# opamp.net
KiCad netlist of a schematic drawn in EAGLE
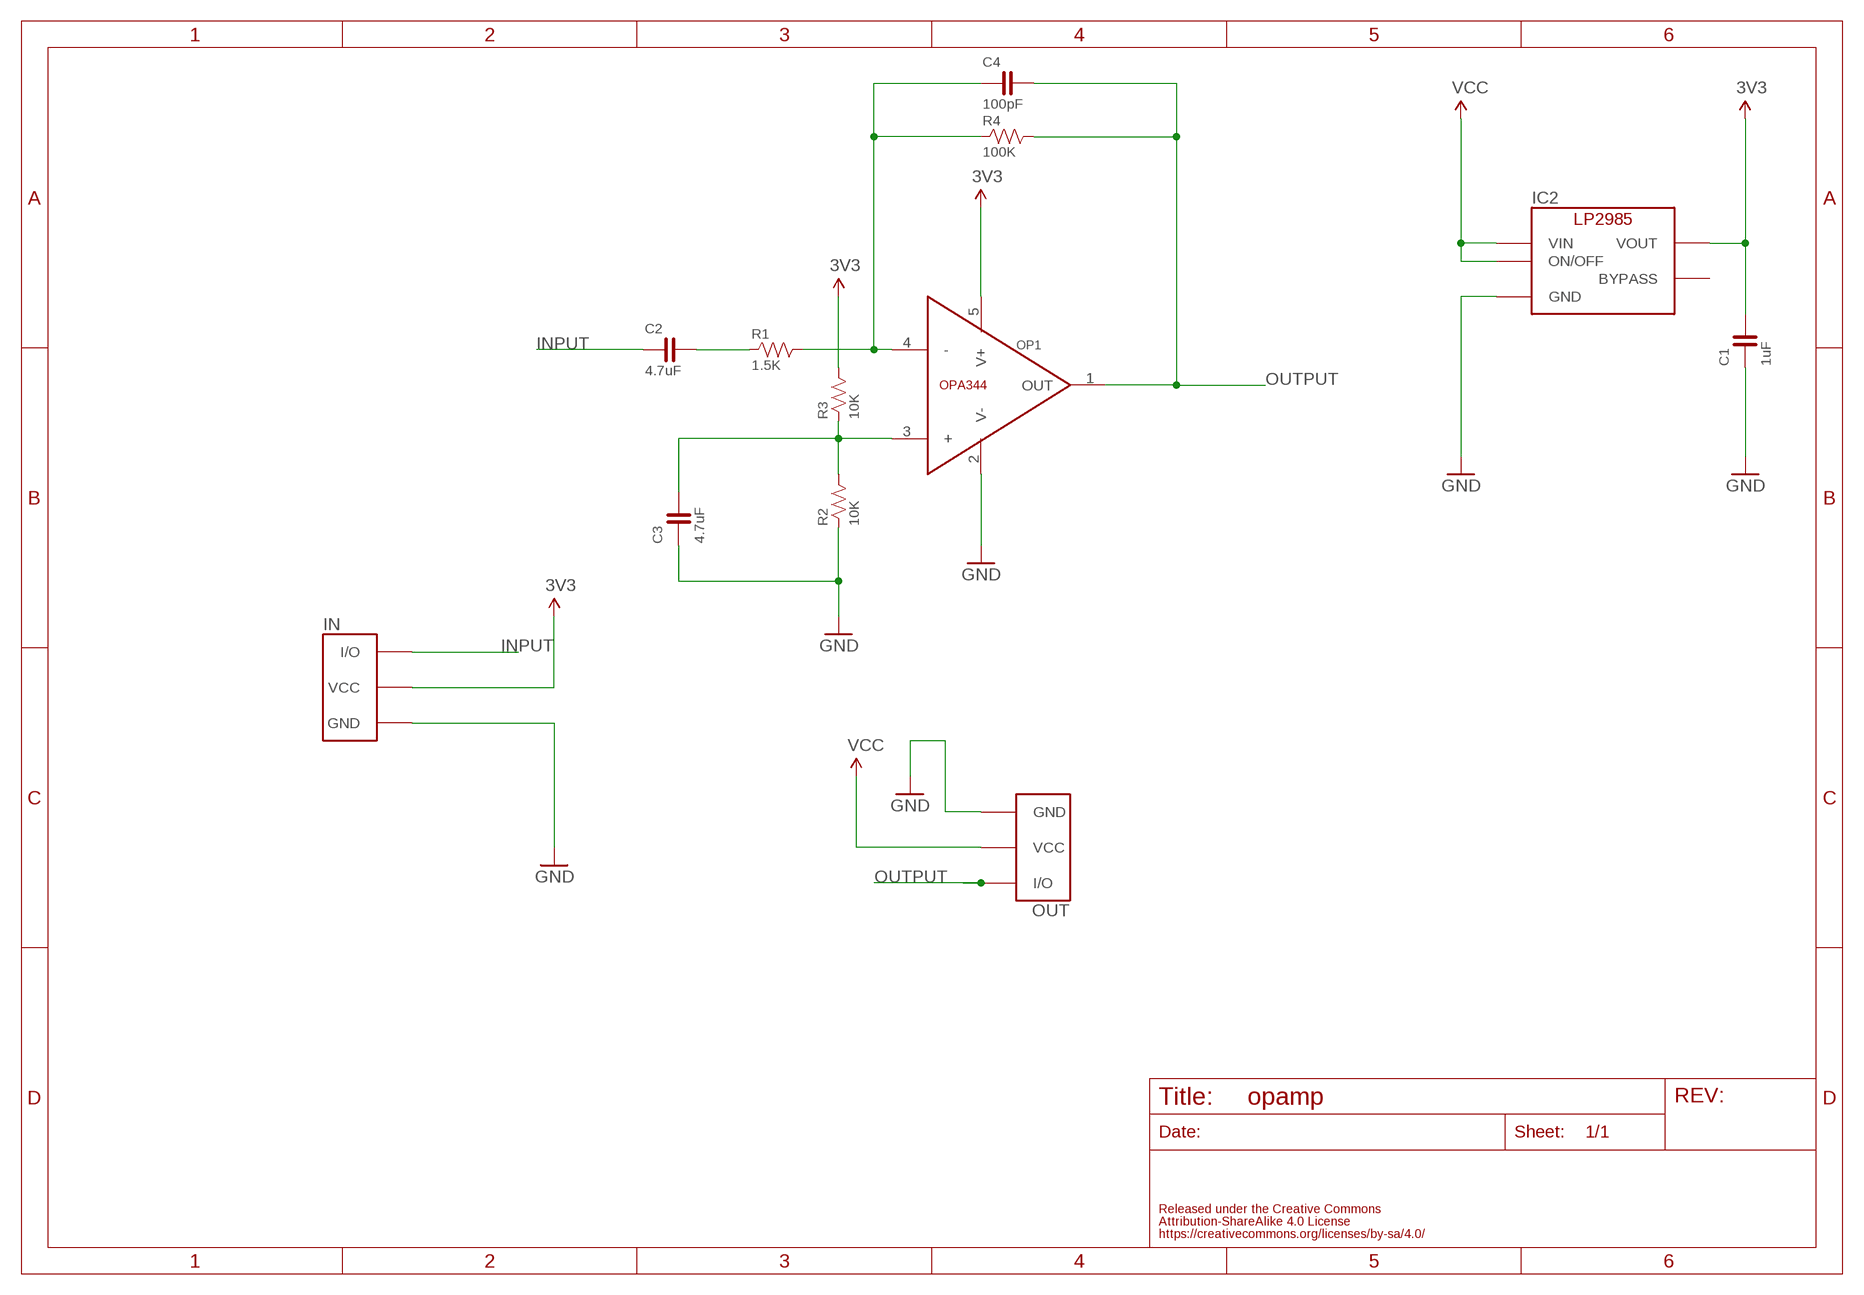
[diagram p0: schematic, sheet 1]

(export (version "E")
  (design (tool "Eeschema 10.0.6"))
  (components
    (comp (ref "C1")
      (value "1uF")
      (footprint "eagle-import:0603")
      (libsource (lib "eagle-import") (part "CAPACITOR-0603"))
    )
    (comp (ref "C2")
      (value "4.7uF")
      (footprint "eagle-import:0603")
      (libsource (lib "eagle-import") (part "CAPACITOR-0603"))
    )
    (comp (ref "C3")
      (value "4.7uF")
      (footprint "eagle-import:0603")
      (libsource (lib "eagle-import") (part "CAPACITOR-0603"))
    )
    (comp (ref "C4")
      (value "100pF")
      (footprint "eagle-import:0603")
      (libsource (lib "eagle-import") (part "CAPACITOR-0603"))
    )
    (comp (ref "IC2")
      (value "LP2985-33DBV")
      (footprint "eagle-import:SOT-23-5")
      (libsource (lib "eagle-import") (part "LP2985-33DBV"))
    )
    (comp (ref "IN")
      (value "FABO_BRICK_3PIN-S03B-PASK-2")
      (footprint "eagle-import:FABO_BRICK_3PIN_S03B-PASK-2")
      (libsource (lib "eagle-import") (part "FABO_BRICK_3PIN-S03B-PASK-2"))
    )
    (comp (ref "OP1")
      (value "OPA344")
      (footprint "eagle-import:SOT23-5")
      (libsource (lib "eagle-import") (part "OPA344"))
    )
    (comp (ref "OUT")
      (value "FABO_BRICK_3PIN-S03B-PASK-2")
      (footprint "eagle-import:FABO_BRICK_3PIN_S03B-PASK-2")
      (libsource (lib "eagle-import") (part "FABO_BRICK_3PIN-S03B-PASK-2"))
    )
    (comp (ref "R1")
      (value "1.5K")
      (footprint "eagle-import:0603")
      (libsource (lib "eagle-import") (part "RESISTOR-0603"))
    )
    (comp (ref "R2")
      (value "10K")
      (footprint "eagle-import:0603")
      (libsource (lib "eagle-import") (part "RESISTOR-0603"))
    )
    (comp (ref "R3")
      (value "10K")
      (footprint "eagle-import:0603")
      (libsource (lib "eagle-import") (part "RESISTOR-0603"))
    )
    (comp (ref "R4")
      (value "100K")
      (footprint "eagle-import:0603")
      (libsource (lib "eagle-import") (part "RESISTOR-0603"))
    )
  )
  (nets
    (net (code "1") (name "/INPUT") (class "Default")
      (node (ref "C2") (pin "1") (pinfunction "1_1") (pintype "passive"))
      (node (ref "IN") (pin "I/O") (pinfunction "I/O_I/O") (pintype "bidirectional"))
    )
    (net (code "2") (name "/OUTPUT") (class "Default")
      (node (ref "C4") (pin "2") (pinfunction "2_2") (pintype "passive"))
      (node (ref "OP1") (pin "1") (pinfunction "OUT_1") (pintype "bidirectional"))
      (node (ref "OUT") (pin "I/O") (pinfunction "I/O_I/O") (pintype "bidirectional"))
      (node (ref "R4") (pin "2") (pinfunction "2_2") (pintype "bidirectional"))
    )
    (net (code "3") (name "3V3") (class "Default")
      (node (ref "C1") (pin "2") (pinfunction "2_2") (pintype "passive"))
      (node (ref "IC2") (pin "5") (pinfunction "VOUT_5") (pintype "output"))
      (node (ref "IN") (pin "VCC") (pinfunction "VCC_VCC") (pintype "bidirectional"))
      (node (ref "OP1") (pin "5") (pinfunction "V+_5") (pintype "bidirectional"))
      (node (ref "R3") (pin "2") (pinfunction "2_2") (pintype "bidirectional"))
    )
    (net (code "4") (name "GND") (class "Default")
      (node (ref "C1") (pin "1") (pinfunction "1_1") (pintype "passive"))
      (node (ref "C3") (pin "1") (pinfunction "1_1") (pintype "passive"))
      (node (ref "IC2") (pin "2") (pinfunction "GND_2") (pintype "power_in"))
      (node (ref "IN") (pin "GND") (pinfunction "GND_GND") (pintype "bidirectional"))
      (node (ref "OP1") (pin "2") (pinfunction "V-_2") (pintype "bidirectional"))
      (node (ref "OUT") (pin "GND") (pinfunction "GND_GND") (pintype "bidirectional"))
      (node (ref "R2") (pin "1") (pinfunction "1_1") (pintype "bidirectional"))
    )
    (net (code "5") (name "Net-(C2-Pad2)") (class "Default")
      (node (ref "C2") (pin "2") (pinfunction "2_2") (pintype "passive"))
      (node (ref "R1") (pin "1") (pinfunction "1_1") (pintype "bidirectional"))
    )
    (net (code "6") (name "Net-(OP1-+)") (class "Default")
      (node (ref "C3") (pin "2") (pinfunction "2_2") (pintype "passive"))
      (node (ref "OP1") (pin "3") (pinfunction "+_3") (pintype "bidirectional"))
      (node (ref "R2") (pin "2") (pinfunction "2_2") (pintype "bidirectional"))
      (node (ref "R3") (pin "1") (pinfunction "1_1") (pintype "bidirectional"))
    )
    (net (code "7") (name "Net-(OP1--)") (class "Default")
      (node (ref "C4") (pin "1") (pinfunction "1_1") (pintype "passive"))
      (node (ref "OP1") (pin "4") (pinfunction "-_4") (pintype "bidirectional"))
      (node (ref "R1") (pin "2") (pinfunction "2_2") (pintype "bidirectional"))
      (node (ref "R4") (pin "1") (pinfunction "1_1") (pintype "bidirectional"))
    )
    (net (code "8") (name "VCC") (class "Default")
      (node (ref "IC2") (pin "1") (pinfunction "VIN_1") (pintype "input"))
      (node (ref "IC2") (pin "3") (pinfunction "ON/OFF_3") (pintype "input"))
      (node (ref "OUT") (pin "VCC") (pinfunction "VCC_VCC") (pintype "bidirectional"))
    )
    (net (code "9") (name "unconnected-(IC2-BYPASS-Pad4)") (class "Default")
      (node (ref "IC2") (pin "4") (pinfunction "BYPASS_4") (pintype "bidirectional"))
    )
  )
)
